# LB_w19_SPLIT_IN-v03_rev2_2_-OHW.net
KiCad netlist of a schematic drawn in EAGLE
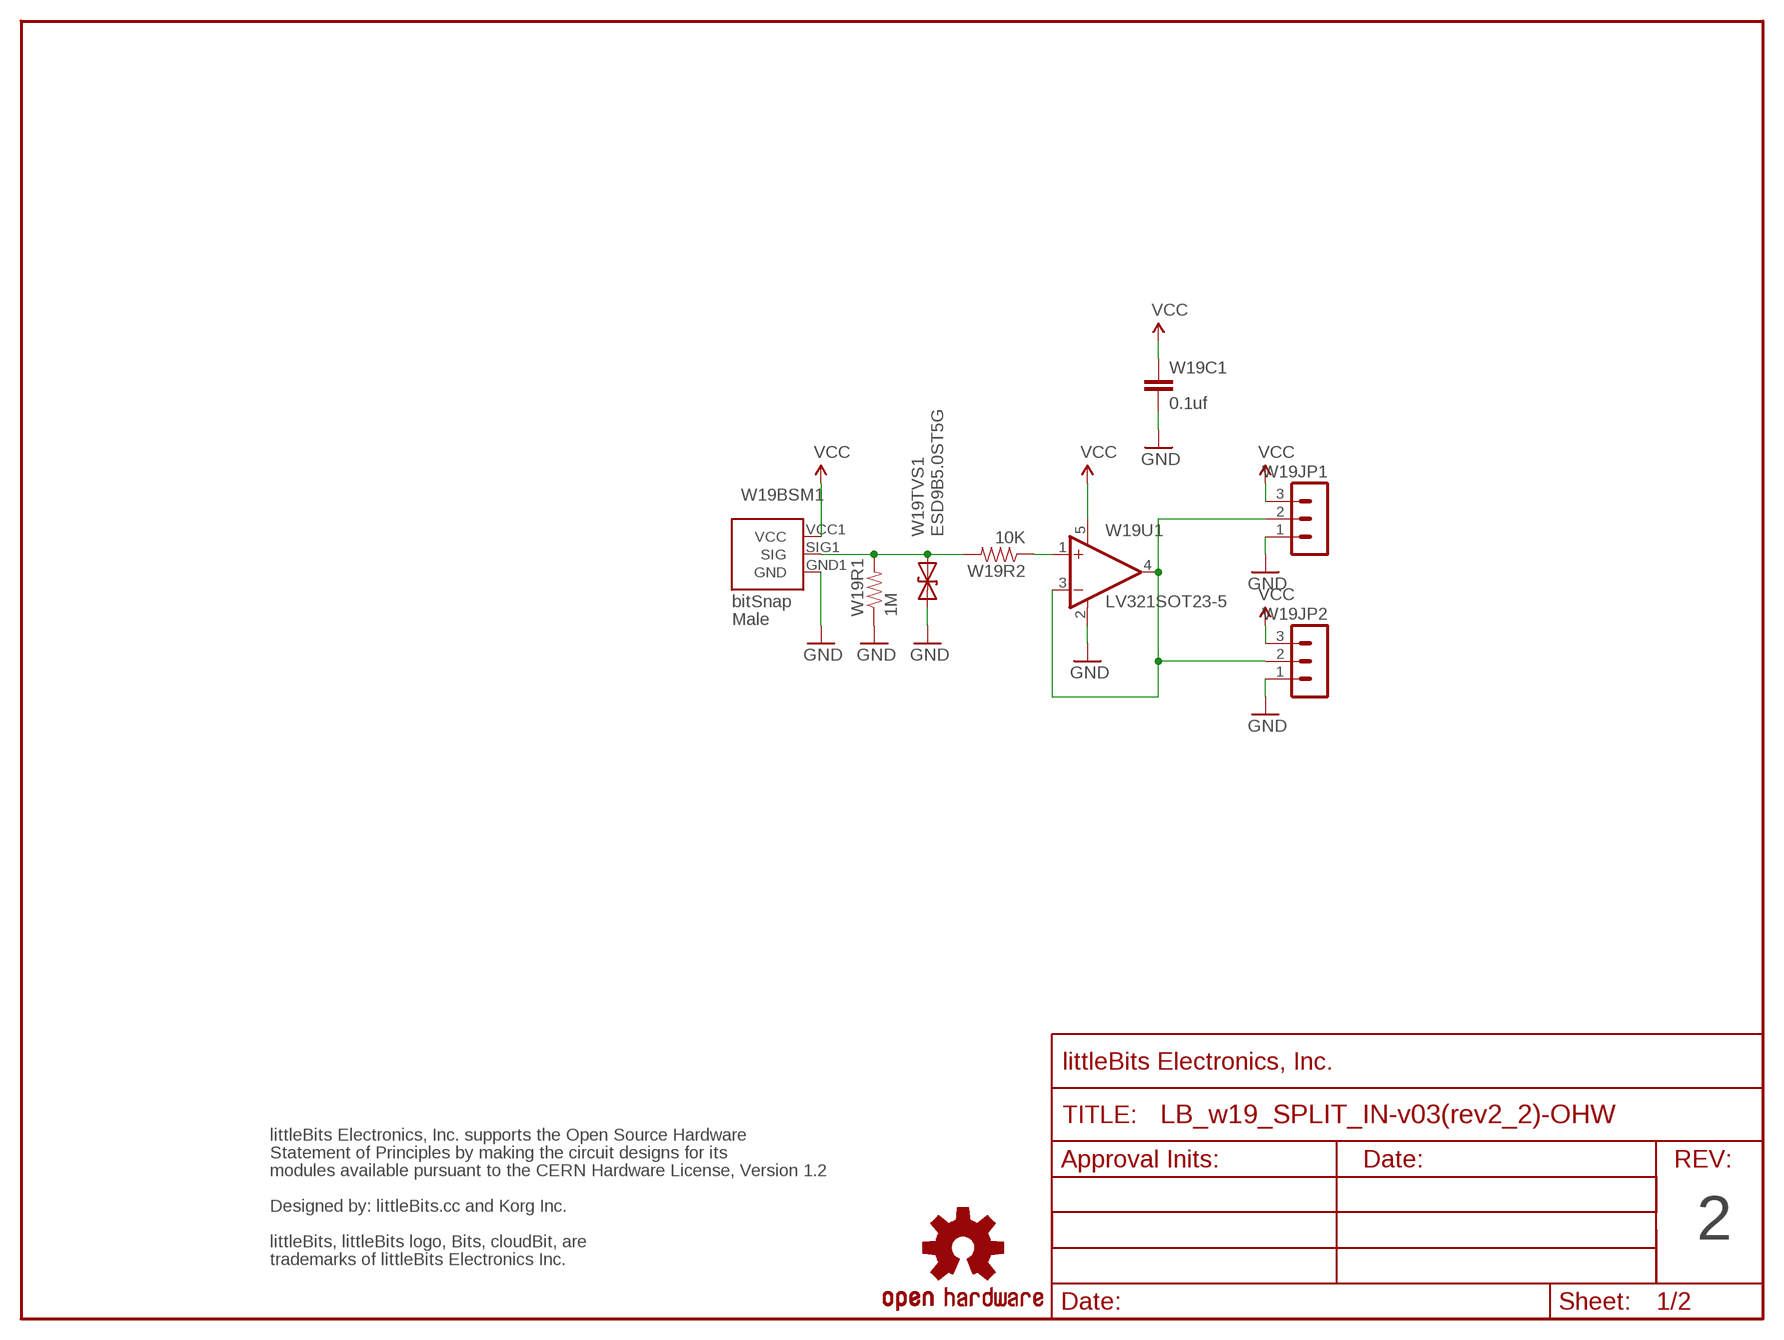
[diagram p0: schematic, sheet 1]

(export (version "E")
  (design (tool "Eeschema 10.0.6"))
  (components
    (comp (ref "FRAME1")
      (value "FRAME-LETTER-OHWOHW")
      (footprint "eagle-import:FABDWG01-OHW")
      (libsource (lib "eagle-import") (part "FRAME-LETTER-OHWOHW"))
    )
    (comp (ref "U$3")
      (value "OSHW-LOGOL")
      (footprint "eagle-import:OSHW-LOGO-L")
      (libsource (lib "eagle-import") (part "OSHW-LOGOL"))
    )
    (comp (ref "U$4")
      (value "OSHWCREDIT-KORG")
      (footprint "eagle-import:OSHWCREDIT-KORG")
      (libsource (lib "eagle-import") (part "OSHWCREDIT-KORG"))
    )
    (comp (ref "W19BSM1")
      (value "BITSNAP_V03_MALE")
      (footprint "eagle-import:BITSNAP_V03_MALE")
      (libsource (lib "eagle-import") (part "BITSNAP_V03_MALE"))
    )
    (comp (ref "W19C1")
      (value "0.1uf")
      (footprint "eagle-import:CAP-0603")
      (libsource (lib "eagle-import") (part "CAPCAP-0603"))
    )
    (comp (ref "W19JP1")
      (value "MA03-1SMD")
      (footprint "eagle-import:1X03-1MM-RA")
      (libsource (lib "eagle-import") (part "MA03-1SMD"))
    )
    (comp (ref "W19JP2")
      (value "MA03-1SMD")
      (footprint "eagle-import:1X03-1MM-RA")
      (libsource (lib "eagle-import") (part "MA03-1SMD"))
    )
    (comp (ref "W19R1")
      (value "1M")
      (footprint "eagle-import:RES-0603")
      (libsource (lib "eagle-import") (part "RESISTOR0603"))
    )
    (comp (ref "W19R2")
      (value "10K")
      (footprint "eagle-import:RES-0603")
      (libsource (lib "eagle-import") (part "RESISTOR0603"))
    )
    (comp (ref "W19TVS1")
      (value "ESD9B5.0ST5G")
      (footprint "eagle-import:SOD-923")
      (libsource (lib "eagle-import") (part "DIODE-TVSSOD-923"))
    )
    (comp (ref "W19U1")
      (value "LV321SOT23-5")
      (footprint "eagle-import:SOT23-5")
      (libsource (lib "eagle-import") (part "LV321SOT23-5"))
    )
  )
  (nets
    (net (code "1") (name "GND") (class "Default")
      (node (ref "W19BSM1") (pin "GND1") (pinfunction "GND_GND1") (pintype "bidirectional"))
      (node (ref "W19C1") (pin "2") (pinfunction "2_2") (pintype "passive"))
      (node (ref "W19JP1") (pin "1") (pinfunction "1_1") (pintype "passive"))
      (node (ref "W19JP2") (pin "1") (pinfunction "1_1") (pintype "passive"))
      (node (ref "W19R1") (pin "1") (pinfunction "1_1") (pintype "passive"))
      (node (ref "W19TVS1") (pin "1") (pinfunction "A_1") (pintype "passive"))
      (node (ref "W19U1") (pin "2") (pinfunction "V-_2") (pintype "power_in"))
    )
    (net (code "2") (name "Net-(W19BSM1-SIG)") (class "Default")
      (node (ref "W19BSM1") (pin "SIG1") (pinfunction "SIG_SIG1") (pintype "bidirectional"))
      (node (ref "W19R1") (pin "2") (pinfunction "2_2") (pintype "passive"))
      (node (ref "W19R2") (pin "2") (pinfunction "2_2") (pintype "passive"))
      (node (ref "W19TVS1") (pin "2") (pinfunction "C_2") (pintype "passive"))
    )
    (net (code "3") (name "Net-(W19U1-+IN)") (class "Default")
      (node (ref "W19R2") (pin "1") (pinfunction "1_1") (pintype "passive"))
      (node (ref "W19U1") (pin "1") (pinfunction "+IN_1") (pintype "input"))
    )
    (net (code "4") (name "Net-(W19U1--IN)") (class "Default")
      (node (ref "W19JP1") (pin "2") (pinfunction "2_2") (pintype "passive"))
      (node (ref "W19JP2") (pin "2") (pinfunction "2_2") (pintype "passive"))
      (node (ref "W19U1") (pin "3") (pinfunction "-IN_3") (pintype "input"))
      (node (ref "W19U1") (pin "4") (pinfunction "OUT_4") (pintype "output"))
    )
    (net (code "5") (name "VCC") (class "Default")
      (node (ref "W19BSM1") (pin "VCC1") (pinfunction "VCC_VCC1") (pintype "bidirectional"))
      (node (ref "W19C1") (pin "1") (pinfunction "1_1") (pintype "passive"))
      (node (ref "W19JP1") (pin "3") (pinfunction "3_3") (pintype "passive"))
      (node (ref "W19JP2") (pin "3") (pinfunction "3_3") (pintype "passive"))
      (node (ref "W19U1") (pin "5") (pinfunction "V+_5") (pintype "power_in"))
    )
  )
)
